# LED_Connection.net
KiCad netlist of a schematic drawn in Altium Designer
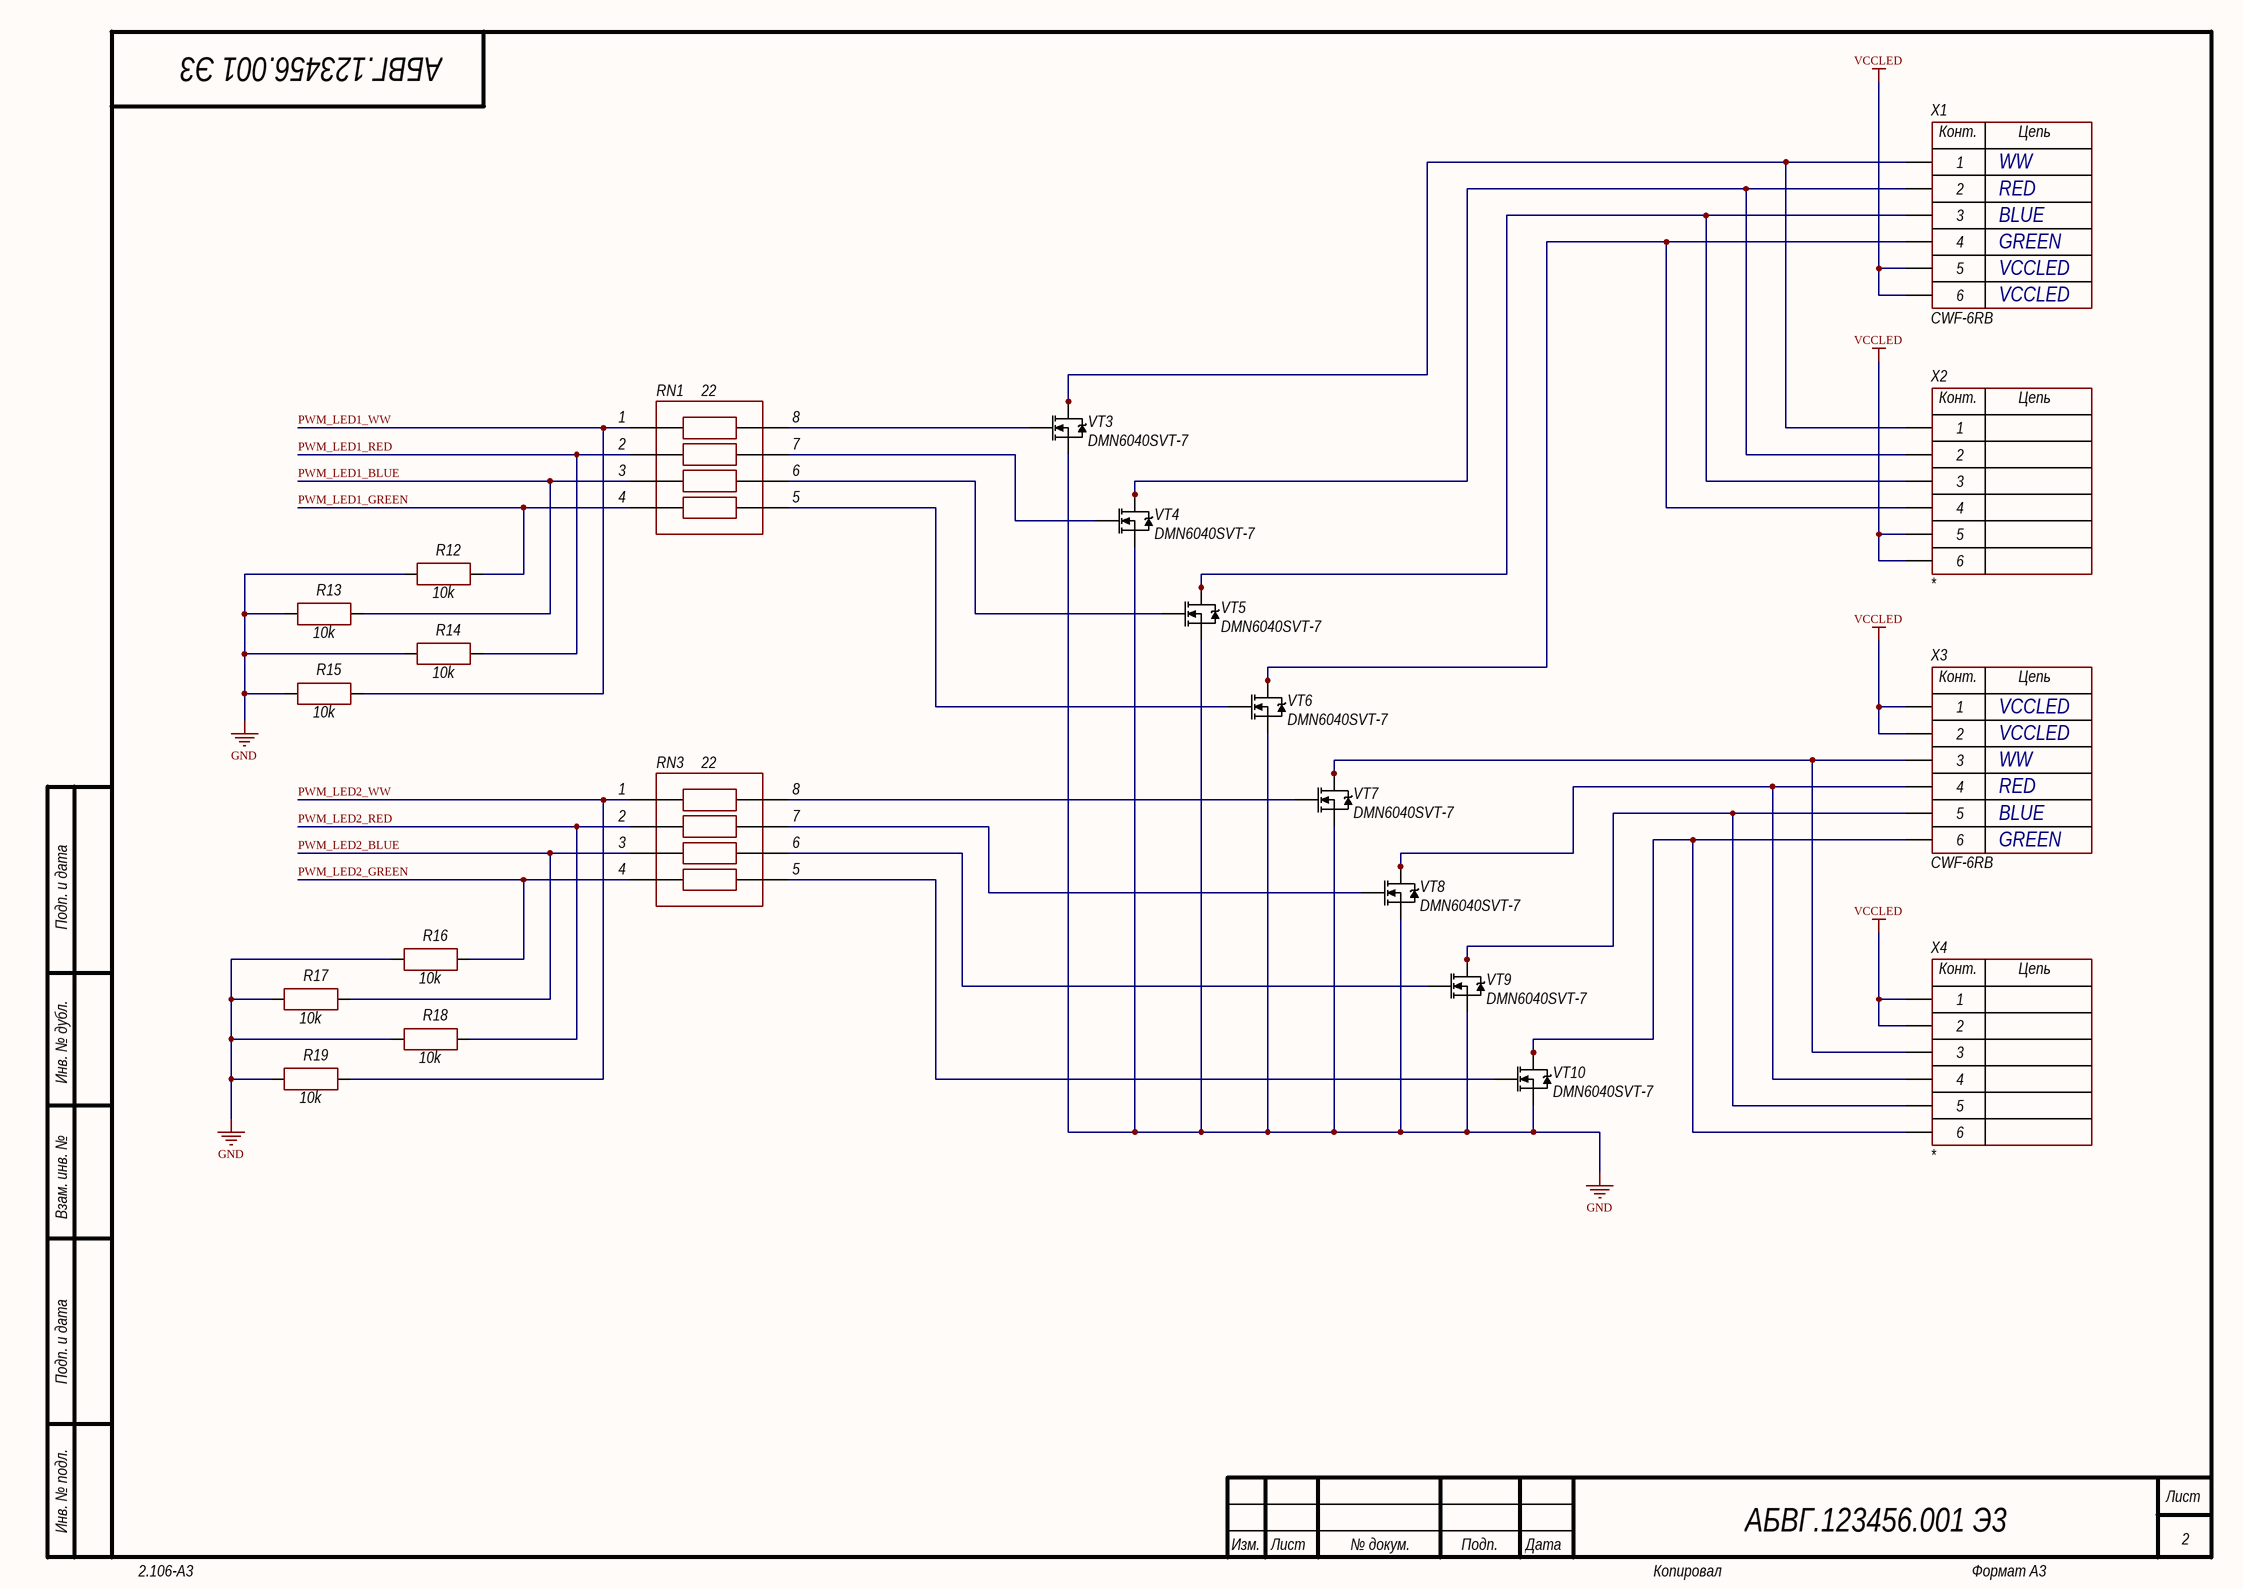
[diagram p0: LED Connection.SchDoc]

(export (version "E")
  (design (tool "Eeschema 10.0.6"))
  (components
    (comp (ref "R12") (value "10k") (footprint "CH0603R") (libsource (lib "Discrete") (part "Resistor")))
    (comp (ref "R13") (value "10k") (footprint "CH0603R") (libsource (lib "Discrete") (part "Resistor")))
    (comp (ref "R14") (value "10k") (footprint "CH0603R") (libsource (lib "Discrete") (part "Resistor")))
    (comp (ref "R15") (value "10k") (footprint "CH0603R") (libsource (lib "Discrete") (part "Resistor")))
    (comp (ref "R16") (value "10k") (footprint "CH0603R") (libsource (lib "Discrete") (part "Resistor")))
    (comp (ref "R17") (value "10k") (footprint "CH0603R") (libsource (lib "Discrete") (part "Resistor")))
    (comp (ref "R18") (value "10k") (footprint "CH0603R") (libsource (lib "Discrete") (part "Resistor")))
    (comp (ref "R19") (value "10k") (footprint "CH0603R") (libsource (lib "Discrete") (part "Resistor")))
    (comp (ref "RN1")
      (value "22")
      (footprint "CH0603Rx4 (1206)")
      (fields (field (name "MANUFACTURER") "Bourns GmbH."))
      (libsource (lib "Discrete") (part "Resistor assembly"))
    )
    (comp (ref "RN3")
      (value "22")
      (footprint "CH0603Rx4 (1206)")
      (fields (field (name "MANUFACTURER") "Bourns GmbH."))
      (libsource (lib "Discrete") (part "Resistor assembly"))
    )
    (comp (ref "VT3")
      (value "DMN6040SVT-7")
      (footprint "TSOT23-6")
      (description "Mosfet")
      (fields (field (name "MANUFACTURER") "Diodes Incorporated"))
      (libsource (lib "Transistor") (part "DMN6040SVT-7"))
    )
    (comp (ref "VT4")
      (value "DMN6040SVT-7")
      (footprint "TSOT23-6")
      (description "Mosfet")
      (fields (field (name "MANUFACTURER") "Diodes Incorporated"))
      (libsource (lib "Transistor") (part "DMN6040SVT-7"))
    )
    (comp (ref "VT5")
      (value "DMN6040SVT-7")
      (footprint "TSOT23-6")
      (description "Mosfet")
      (fields (field (name "MANUFACTURER") "Diodes Incorporated"))
      (libsource (lib "Transistor") (part "DMN6040SVT-7"))
    )
    (comp (ref "VT6")
      (value "DMN6040SVT-7")
      (footprint "TSOT23-6")
      (description "Mosfet")
      (fields (field (name "MANUFACTURER") "Diodes Incorporated"))
      (libsource (lib "Transistor") (part "DMN6040SVT-7"))
    )
    (comp (ref "VT7")
      (value "DMN6040SVT-7")
      (footprint "TSOT23-6")
      (description "Mosfet")
      (fields (field (name "MANUFACTURER") "Diodes Incorporated"))
      (libsource (lib "Transistor") (part "DMN6040SVT-7"))
    )
    (comp (ref "VT8")
      (value "DMN6040SVT-7")
      (footprint "TSOT23-6")
      (description "Mosfet")
      (fields (field (name "MANUFACTURER") "Diodes Incorporated"))
      (libsource (lib "Transistor") (part "DMN6040SVT-7"))
    )
    (comp (ref "VT9")
      (value "DMN6040SVT-7")
      (footprint "TSOT23-6")
      (description "Mosfet")
      (fields (field (name "MANUFACTURER") "Diodes Incorporated"))
      (libsource (lib "Transistor") (part "DMN6040SVT-7"))
    )
    (comp (ref "VT10")
      (value "DMN6040SVT-7")
      (footprint "TSOT23-6")
      (description "Mosfet")
      (fields (field (name "MANUFACTURER") "Diodes Incorporated"))
      (libsource (lib "Transistor") (part "DMN6040SVT-7"))
    )
    (comp (ref "X1")
      (value "CWF-6RB")
      (footprint "CON: CWF-6RB")
      (libsource (lib "Connectors") (part "6-Connector"))
    )
    (comp (ref "X2") (value "*") (footprint "CON: PBS-6") (libsource (lib "Connectors") (part "6-Connector")))
    (comp (ref "X3")
      (value "CWF-6RB")
      (footprint "CON: CWF-6RB")
      (libsource (lib "Connectors") (part "6-Connector"))
    )
    (comp (ref "X4") (value "*") (footprint "CON: PBS-6") (libsource (lib "Connectors") (part "6-Connector")))
  )
  (nets
    (net (code "1") (name "/PWM_LED1_BLUE") (class "Default")
      (node (ref "R13") (pin "2") (pinfunction "2_2") (pintype "passive"))
      (node (ref "RN1") (pin "3") (pinfunction "3_3") (pintype "passive"))
    )
    (net (code "2") (name "/PWM_LED1_GREEN") (class "Default")
      (node (ref "R12") (pin "2") (pinfunction "2_2") (pintype "passive"))
      (node (ref "RN1") (pin "4") (pinfunction "4_4") (pintype "passive"))
    )
    (net (code "3") (name "/PWM_LED1_RED") (class "Default")
      (node (ref "R14") (pin "2") (pinfunction "2_2") (pintype "passive"))
      (node (ref "RN1") (pin "2") (pinfunction "2_2") (pintype "passive"))
    )
    (net (code "4") (name "/PWM_LED1_WW") (class "Default")
      (node (ref "R15") (pin "2") (pinfunction "2_2") (pintype "passive"))
      (node (ref "RN1") (pin "1") (pinfunction "1_1") (pintype "passive"))
    )
    (net (code "5") (name "/PWM_LED2_BLUE") (class "Default")
      (node (ref "R17") (pin "2") (pinfunction "2_2") (pintype "passive"))
      (node (ref "RN3") (pin "3") (pinfunction "3_3") (pintype "passive"))
    )
    (net (code "6") (name "/PWM_LED2_GREEN") (class "Default")
      (node (ref "R16") (pin "2") (pinfunction "2_2") (pintype "passive"))
      (node (ref "RN3") (pin "4") (pinfunction "4_4") (pintype "passive"))
    )
    (net (code "7") (name "/PWM_LED2_RED") (class "Default")
      (node (ref "R18") (pin "2") (pinfunction "2_2") (pintype "passive"))
      (node (ref "RN3") (pin "2") (pinfunction "2_2") (pintype "passive"))
    )
    (net (code "8") (name "/PWM_LED2_WW") (class "Default")
      (node (ref "R19") (pin "2") (pinfunction "2_2") (pintype "passive"))
      (node (ref "RN3") (pin "1") (pinfunction "1_1") (pintype "passive"))
    )
    (net (code "9") (name "GND") (class "Default")
      (node (ref "R12") (pin "1") (pinfunction "1_1") (pintype "passive"))
      (node (ref "R13") (pin "1") (pinfunction "1_1") (pintype "passive"))
      (node (ref "R14") (pin "1") (pinfunction "1_1") (pintype "passive"))
      (node (ref "R15") (pin "1") (pinfunction "1_1") (pintype "passive"))
      (node (ref "R16") (pin "1") (pinfunction "1_1") (pintype "passive"))
      (node (ref "R17") (pin "1") (pinfunction "1_1") (pintype "passive"))
      (node (ref "R18") (pin "1") (pinfunction "1_1") (pintype "passive"))
      (node (ref "R19") (pin "1") (pinfunction "1_1") (pintype "passive"))
      (node (ref "VT10") (pin "4") (pinfunction "S_4") (pintype "passive"))
      (node (ref "VT3") (pin "4") (pinfunction "S_4") (pintype "passive"))
      (node (ref "VT4") (pin "4") (pinfunction "S_4") (pintype "passive"))
      (node (ref "VT5") (pin "4") (pinfunction "S_4") (pintype "passive"))
      (node (ref "VT6") (pin "4") (pinfunction "S_4") (pintype "passive"))
      (node (ref "VT7") (pin "4") (pinfunction "S_4") (pintype "passive"))
      (node (ref "VT8") (pin "4") (pinfunction "S_4") (pintype "passive"))
      (node (ref "VT9") (pin "4") (pinfunction "S_4") (pintype "passive"))
    )
    (net (code "10") (name "Net-(VT3-D-Pad1)") (class "Default")
      (node (ref "VT3") (pin "1") (pinfunction "D_1") (pintype "passive"))
      (node (ref "VT3") (pin "2") (pinfunction "D_2") (pintype "passive"))
      (node (ref "VT3") (pin "5") (pinfunction "D_5") (pintype "passive"))
      (node (ref "VT3") (pin "6") (pinfunction "D_6") (pintype "passive"))
      (node (ref "X1") (pin "1") (pinfunction "1_1") (pintype "passive"))
      (node (ref "X2") (pin "1") (pinfunction "1_1") (pintype "passive"))
    )
    (net (code "11") (name "Net-(VT3-G)") (class "Default")
      (node (ref "RN1") (pin "8") (pinfunction "8_8") (pintype "passive"))
      (node (ref "VT3") (pin "3") (pinfunction "G_3") (pintype "passive"))
    )
    (net (code "12") (name "Net-(VT4-D-Pad1)") (class "Default")
      (node (ref "VT4") (pin "1") (pinfunction "D_1") (pintype "passive"))
      (node (ref "VT4") (pin "2") (pinfunction "D_2") (pintype "passive"))
      (node (ref "VT4") (pin "5") (pinfunction "D_5") (pintype "passive"))
      (node (ref "VT4") (pin "6") (pinfunction "D_6") (pintype "passive"))
      (node (ref "X1") (pin "2") (pinfunction "2_2") (pintype "passive"))
      (node (ref "X2") (pin "2") (pinfunction "2_2") (pintype "passive"))
    )
    (net (code "13") (name "Net-(VT4-G)") (class "Default")
      (node (ref "RN1") (pin "7") (pinfunction "7_7") (pintype "passive"))
      (node (ref "VT4") (pin "3") (pinfunction "G_3") (pintype "passive"))
    )
    (net (code "14") (name "Net-(VT5-D-Pad1)") (class "Default")
      (node (ref "VT5") (pin "1") (pinfunction "D_1") (pintype "passive"))
      (node (ref "VT5") (pin "2") (pinfunction "D_2") (pintype "passive"))
      (node (ref "VT5") (pin "5") (pinfunction "D_5") (pintype "passive"))
      (node (ref "VT5") (pin "6") (pinfunction "D_6") (pintype "passive"))
      (node (ref "X1") (pin "3") (pinfunction "3_3") (pintype "power_in"))
      (node (ref "X2") (pin "3") (pinfunction "3_3") (pintype "power_in"))
    )
    (net (code "15") (name "Net-(VT5-G)") (class "Default")
      (node (ref "RN1") (pin "6") (pinfunction "6_6") (pintype "passive"))
      (node (ref "VT5") (pin "3") (pinfunction "G_3") (pintype "passive"))
    )
    (net (code "16") (name "Net-(VT6-D-Pad1)") (class "Default")
      (node (ref "VT6") (pin "1") (pinfunction "D_1") (pintype "passive"))
      (node (ref "VT6") (pin "2") (pinfunction "D_2") (pintype "passive"))
      (node (ref "VT6") (pin "5") (pinfunction "D_5") (pintype "passive"))
      (node (ref "VT6") (pin "6") (pinfunction "D_6") (pintype "passive"))
      (node (ref "X1") (pin "4") (pinfunction "4_4") (pintype "power_in"))
      (node (ref "X2") (pin "4") (pinfunction "4_4") (pintype "power_in"))
    )
    (net (code "17") (name "Net-(VT6-G)") (class "Default")
      (node (ref "RN1") (pin "5") (pinfunction "5_5") (pintype "passive"))
      (node (ref "VT6") (pin "3") (pinfunction "G_3") (pintype "passive"))
    )
    (net (code "18") (name "Net-(VT7-D-Pad1)") (class "Default")
      (node (ref "VT7") (pin "1") (pinfunction "D_1") (pintype "passive"))
      (node (ref "VT7") (pin "2") (pinfunction "D_2") (pintype "passive"))
      (node (ref "VT7") (pin "5") (pinfunction "D_5") (pintype "passive"))
      (node (ref "VT7") (pin "6") (pinfunction "D_6") (pintype "passive"))
      (node (ref "X3") (pin "3") (pinfunction "3_3") (pintype "power_in"))
      (node (ref "X4") (pin "3") (pinfunction "3_3") (pintype "power_in"))
    )
    (net (code "19") (name "Net-(VT7-G)") (class "Default")
      (node (ref "RN3") (pin "8") (pinfunction "8_8") (pintype "passive"))
      (node (ref "VT7") (pin "3") (pinfunction "G_3") (pintype "passive"))
    )
    (net (code "20") (name "Net-(VT8-D-Pad1)") (class "Default")
      (node (ref "VT8") (pin "1") (pinfunction "D_1") (pintype "passive"))
      (node (ref "VT8") (pin "2") (pinfunction "D_2") (pintype "passive"))
      (node (ref "VT8") (pin "5") (pinfunction "D_5") (pintype "passive"))
      (node (ref "VT8") (pin "6") (pinfunction "D_6") (pintype "passive"))
      (node (ref "X3") (pin "4") (pinfunction "4_4") (pintype "power_in"))
      (node (ref "X4") (pin "4") (pinfunction "4_4") (pintype "power_in"))
    )
    (net (code "21") (name "Net-(VT8-G)") (class "Default")
      (node (ref "RN3") (pin "7") (pinfunction "7_7") (pintype "passive"))
      (node (ref "VT8") (pin "3") (pinfunction "G_3") (pintype "passive"))
    )
    (net (code "22") (name "Net-(VT9-D-Pad1)") (class "Default")
      (node (ref "VT9") (pin "1") (pinfunction "D_1") (pintype "passive"))
      (node (ref "VT9") (pin "2") (pinfunction "D_2") (pintype "passive"))
      (node (ref "VT9") (pin "5") (pinfunction "D_5") (pintype "passive"))
      (node (ref "VT9") (pin "6") (pinfunction "D_6") (pintype "passive"))
      (node (ref "X3") (pin "5") (pinfunction "5_5") (pintype "power_in"))
      (node (ref "X4") (pin "5") (pinfunction "5_5") (pintype "power_in"))
    )
    (net (code "23") (name "Net-(VT9-G)") (class "Default")
      (node (ref "RN3") (pin "6") (pinfunction "6_6") (pintype "passive"))
      (node (ref "VT9") (pin "3") (pinfunction "G_3") (pintype "passive"))
    )
    (net (code "24") (name "Net-(VT10-D-Pad1)") (class "Default")
      (node (ref "VT10") (pin "1") (pinfunction "D_1") (pintype "passive"))
      (node (ref "VT10") (pin "2") (pinfunction "D_2") (pintype "passive"))
      (node (ref "VT10") (pin "5") (pinfunction "D_5") (pintype "passive"))
      (node (ref "VT10") (pin "6") (pinfunction "D_6") (pintype "passive"))
      (node (ref "X3") (pin "6") (pinfunction "6_6") (pintype "power_in"))
      (node (ref "X4") (pin "6") (pinfunction "6_6") (pintype "power_in"))
    )
    (net (code "25") (name "Net-(VT10-G)") (class "Default")
      (node (ref "RN3") (pin "5") (pinfunction "5_5") (pintype "passive"))
      (node (ref "VT10") (pin "3") (pinfunction "G_3") (pintype "passive"))
    )
    (net (code "26") (name "VCCLED") (class "Default")
      (node (ref "X1") (pin "5") (pinfunction "5_5") (pintype "power_in"))
      (node (ref "X1") (pin "6") (pinfunction "6_6") (pintype "power_in"))
      (node (ref "X2") (pin "5") (pinfunction "5_5") (pintype "power_in"))
      (node (ref "X2") (pin "6") (pinfunction "6_6") (pintype "power_in"))
      (node (ref "X3") (pin "1") (pinfunction "1_1") (pintype "passive"))
      (node (ref "X3") (pin "2") (pinfunction "2_2") (pintype "passive"))
      (node (ref "X4") (pin "1") (pinfunction "1_1") (pintype "passive"))
      (node (ref "X4") (pin "2") (pinfunction "2_2") (pintype "passive"))
    )
  )
)
